# krajBB-Priezvisko_Meno.net
KiCad netlist of a schematic drawn in EAGLE
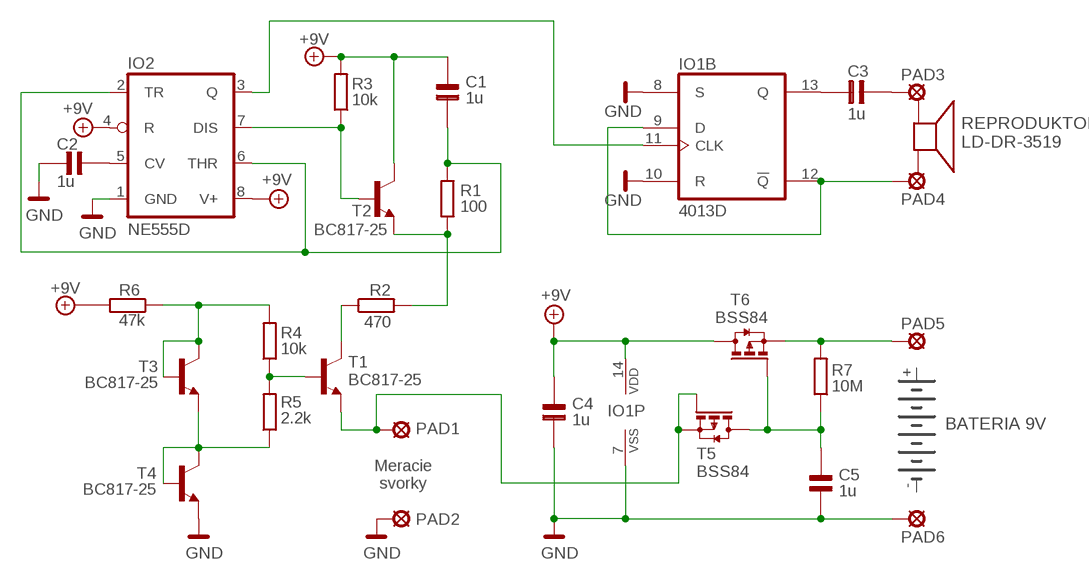
[diagram p0: schematic, sheet 1]

(export (version "E")
  (design (tool "Eeschema 10.0.6"))
  (components
    (comp (ref "C1")
      (value "1u")
      (footprint "eagle-import:1206")
      (libsource (lib "eagle-import") (part "C1206TOP"))
    )
    (comp (ref "C2")
      (value "1u")
      (footprint "eagle-import:1206")
      (libsource (lib "eagle-import") (part "C1206TOP"))
    )
    (comp (ref "C3")
      (value "1u")
      (footprint "eagle-import:1206")
      (libsource (lib "eagle-import") (part "C1206TOP"))
    )
    (comp (ref "C4")
      (value "1u")
      (footprint "eagle-import:1206")
      (libsource (lib "eagle-import") (part "C1206TOP"))
    )
    (comp (ref "C5")
      (value "1u")
      (footprint "eagle-import:1206")
      (libsource (lib "eagle-import") (part "C1206TOP"))
    )
    (comp (ref "IO1")
      (value "4013D")
      (footprint "eagle-import:SO14")
      (libsource (lib "eagle-import") (part "4013D"))
    )
    (comp (ref "IO2")
      (value "NE555D")
      (footprint "eagle-import:SO08")
      (libsource (lib "eagle-import") (part "555DNE"))
    )
    (comp (ref "PAD1")
      (value "SMD3X3")
      (footprint "eagle-import:SMD3X3")
      (libsource (lib "eagle-import") (part "SMD3X3"))
    )
    (comp (ref "PAD2")
      (value "SMD3X3")
      (footprint "eagle-import:SMD3X3")
      (libsource (lib "eagle-import") (part "SMD3X3"))
    )
    (comp (ref "PAD3")
      (value "SMD3X3")
      (footprint "eagle-import:SMD3X3")
      (libsource (lib "eagle-import") (part "SMD3X3"))
    )
    (comp (ref "PAD4")
      (value "SMD3X3")
      (footprint "eagle-import:SMD3X3")
      (libsource (lib "eagle-import") (part "SMD3X3"))
    )
    (comp (ref "PAD5")
      (value "SMD3X3")
      (footprint "eagle-import:SMD3X3")
      (libsource (lib "eagle-import") (part "SMD3X3"))
    )
    (comp (ref "PAD6")
      (value "SMD3X3")
      (footprint "eagle-import:SMD3X3")
      (libsource (lib "eagle-import") (part "SMD3X3"))
    )
    (comp (ref "R1")
      (value "100")
      (footprint "eagle-import:1206")
      (libsource (lib "eagle-import") (part "R1206TOP"))
    )
    (comp (ref "R2")
      (value "470")
      (footprint "eagle-import:1206")
      (libsource (lib "eagle-import") (part "R1206TOP"))
    )
    (comp (ref "R3")
      (value "10k")
      (footprint "eagle-import:1206")
      (libsource (lib "eagle-import") (part "R1206TOP"))
    )
    (comp (ref "R4")
      (value "10k")
      (footprint "eagle-import:1206")
      (libsource (lib "eagle-import") (part "R1206TOP"))
    )
    (comp (ref "R5")
      (value "2.2k")
      (footprint "eagle-import:1206")
      (libsource (lib "eagle-import") (part "R1206TOP"))
    )
    (comp (ref "R6")
      (value "47k")
      (footprint "eagle-import:1206")
      (libsource (lib "eagle-import") (part "R1206TOP"))
    )
    (comp (ref "R7")
      (value "10M")
      (footprint "eagle-import:1206")
      (libsource (lib "eagle-import") (part "R1206TOP"))
    )
    (comp (ref "REPRODUKTOR")
      (value "LD-DR-3519")
      (footprint "eagle-import:LD-DR-3519")
      (libsource (lib "eagle-import") (part "LD-DR-3519"))
    )
    (comp (ref "T1")
      (value "BC817-25")
      (footprint "eagle-import:SOT23-BEC")
      (libsource (lib "eagle-import") (part "BC817SMD-25"))
    )
    (comp (ref "T2")
      (value "BC817-25")
      (footprint "eagle-import:SOT23-BEC")
      (libsource (lib "eagle-import") (part "BC817SMD-25"))
    )
    (comp (ref "T3")
      (value "BC817-25")
      (footprint "eagle-import:SOT23-BEC")
      (libsource (lib "eagle-import") (part "BC817SMD-25"))
    )
    (comp (ref "T4")
      (value "BC817-25")
      (footprint "eagle-import:SOT23-BEC")
      (libsource (lib "eagle-import") (part "BC817SMD-25"))
    )
    (comp (ref "T5")
      (value "BSS84")
      (footprint "eagle-import:SOT23")
      (libsource (lib "eagle-import") (part "BSS84"))
    )
    (comp (ref "T6")
      (value "BSS84")
      (footprint "eagle-import:SOT23")
      (libsource (lib "eagle-import") (part "BSS84"))
    )
    (comp (ref "U$1")
      (value "9VBATTERY")
      (footprint "eagle-import:9VBATTERY")
      (libsource (lib "eagle-import") (part "9VBATTERY"))
    )
  )
  (nets
    (net (code "1") (name "+9V") (class "Default")
      (node (ref "C1") (pin "2") (pinfunction "2_2") (pintype "passive"))
      (node (ref "C4") (pin "2") (pinfunction "2_2") (pintype "passive"))
      (node (ref "IO1") (pin "14") (pinfunction "VDD_14") (pintype "power_in"))
      (node (ref "IO2") (pin "4") (pinfunction "R_4") (pintype "input"))
      (node (ref "IO2") (pin "8") (pinfunction "V+_8") (pintype "power_in"))
      (node (ref "R3") (pin "2") (pinfunction "2_2") (pintype "passive"))
      (node (ref "R6") (pin "2") (pinfunction "2_2") (pintype "passive"))
      (node (ref "T2") (pin "C") (pinfunction "C_C") (pintype "passive"))
      (node (ref "T6") (pin "3") (pinfunction "D_3") (pintype "passive"))
    )
    (net (code "2") (name "GND") (class "Default")
      (node (ref "C2") (pin "1") (pinfunction "1_1") (pintype "passive"))
      (node (ref "C4") (pin "1") (pinfunction "1_1") (pintype "passive"))
      (node (ref "C5") (pin "1") (pinfunction "1_1") (pintype "passive"))
      (node (ref "IO1") (pin "10") (pinfunction "R_10") (pintype "input"))
      (node (ref "IO1") (pin "7") (pinfunction "VSS_7") (pintype "power_in"))
      (node (ref "IO1") (pin "8") (pinfunction "S_8") (pintype "input"))
      (node (ref "IO2") (pin "1") (pinfunction "GND_1") (pintype "power_in"))
      (node (ref "PAD2") (pin "P$1") (pinfunction "MP_P$1") (pintype "passive"))
      (node (ref "PAD6") (pin "P$1") (pinfunction "MP_P$1") (pintype "passive"))
      (node (ref "T4") (pin "E") (pinfunction "E_E") (pintype "passive"))
    )
    (net (code "3") (name "Net-(IO1B-CLK)") (class "Default")
      (node (ref "IO1") (pin "11") (pinfunction "CLK_11") (pintype "input"))
      (node (ref "IO2") (pin "3") (pinfunction "Q_3") (pintype "output"))
    )
    (net (code "4") (name "Net-(IO1B-D)") (class "Default")
      (node (ref "IO1") (pin "12") (pinfunction "~{Q}_12") (pintype "output"))
      (node (ref "IO1") (pin "9") (pinfunction "D_9") (pintype "input"))
      (node (ref "PAD4") (pin "P$1") (pinfunction "MP_P$1") (pintype "passive"))
    )
    (net (code "5") (name "Net-(IO1B-Q)") (class "Default")
      (node (ref "C3") (pin "1") (pinfunction "1_1") (pintype "passive"))
      (node (ref "IO1") (pin "13") (pinfunction "Q_13") (pintype "output"))
    )
    (net (code "6") (name "Net-(IO2-CV)") (class "Default")
      (node (ref "C2") (pin "2") (pinfunction "2_2") (pintype "passive"))
      (node (ref "IO2") (pin "5") (pinfunction "CV_5") (pintype "input"))
    )
    (net (code "7") (name "Net-(IO2-DIS)") (class "Default")
      (node (ref "IO2") (pin "7") (pinfunction "DIS_7") (pintype "input"))
      (node (ref "R3") (pin "1") (pinfunction "1_1") (pintype "passive"))
      (node (ref "T2") (pin "B") (pinfunction "B_B") (pintype "passive"))
    )
    (net (code "8") (name "Net-(IO2-THR)") (class "Default")
      (node (ref "C1") (pin "1") (pinfunction "1_1") (pintype "passive"))
      (node (ref "IO2") (pin "2") (pinfunction "TR_2") (pintype "input"))
      (node (ref "IO2") (pin "6") (pinfunction "THR_6") (pintype "input"))
      (node (ref "R1") (pin "2") (pinfunction "2_2") (pintype "passive"))
    )
    (net (code "9") (name "Net-(PAD1-MP)") (class "Default")
      (node (ref "PAD1") (pin "P$1") (pinfunction "MP_P$1") (pintype "passive"))
      (node (ref "T1") (pin "E") (pinfunction "E_E") (pintype "passive"))
      (node (ref "T5") (pin "1") (pinfunction "G_1") (pintype "passive"))
      (node (ref "T5") (pin "2") (pinfunction "S_2") (pintype "passive"))
    )
    (net (code "10") (name "Net-(PAD3-MP)") (class "Default")
      (node (ref "C3") (pin "2") (pinfunction "2_2") (pintype "passive"))
      (node (ref "PAD3") (pin "P$1") (pinfunction "MP_P$1") (pintype "passive"))
    )
    (net (code "11") (name "Net-(PAD5-MP)") (class "Default")
      (node (ref "PAD5") (pin "P$1") (pinfunction "MP_P$1") (pintype "passive"))
      (node (ref "R7") (pin "2") (pinfunction "2_2") (pintype "passive"))
      (node (ref "T6") (pin "2") (pinfunction "S_2") (pintype "passive"))
    )
    (net (code "12") (name "Net-(R1-Pad1)") (class "Default")
      (node (ref "R1") (pin "1") (pinfunction "1_1") (pintype "passive"))
      (node (ref "R2") (pin "2") (pinfunction "2_2") (pintype "passive"))
      (node (ref "T2") (pin "E") (pinfunction "E_E") (pintype "passive"))
    )
    (net (code "13") (name "Net-(R2-Pad1)") (class "Default")
      (node (ref "R2") (pin "1") (pinfunction "1_1") (pintype "passive"))
      (node (ref "T1") (pin "C") (pinfunction "C_C") (pintype "passive"))
    )
    (net (code "14") (name "Net-(R4-Pad1)") (class "Default")
      (node (ref "R4") (pin "1") (pinfunction "1_1") (pintype "passive"))
      (node (ref "R5") (pin "2") (pinfunction "2_2") (pintype "passive"))
      (node (ref "T1") (pin "B") (pinfunction "B_B") (pintype "passive"))
    )
    (net (code "15") (name "Net-(R4-Pad2)") (class "Default")
      (node (ref "R4") (pin "2") (pinfunction "2_2") (pintype "passive"))
      (node (ref "R6") (pin "1") (pinfunction "1_1") (pintype "passive"))
      (node (ref "T3") (pin "B") (pinfunction "B_B") (pintype "passive"))
      (node (ref "T3") (pin "C") (pinfunction "C_C") (pintype "passive"))
    )
    (net (code "16") (name "Net-(R5-Pad1)") (class "Default")
      (node (ref "R5") (pin "1") (pinfunction "1_1") (pintype "passive"))
      (node (ref "T3") (pin "E") (pinfunction "E_E") (pintype "passive"))
      (node (ref "T4") (pin "B") (pinfunction "B_B") (pintype "passive"))
      (node (ref "T4") (pin "C") (pinfunction "C_C") (pintype "passive"))
    )
    (net (code "17") (name "Net-(T5-D)") (class "Default")
      (node (ref "C5") (pin "2") (pinfunction "2_2") (pintype "passive"))
      (node (ref "R7") (pin "1") (pinfunction "1_1") (pintype "passive"))
      (node (ref "T5") (pin "3") (pinfunction "D_3") (pintype "passive"))
      (node (ref "T6") (pin "1") (pinfunction "G_1") (pintype "passive"))
    )
    (net (code "18") (name "unconnected-(REPRODUKTOR-1-PadP$1)") (class "Default")
      (node (ref "REPRODUKTOR") (pin "P$1") (pinfunction "1_P$1") (pintype "passive"))
    )
    (net (code "19") (name "unconnected-(REPRODUKTOR-2-PadP$2)") (class "Default")
      (node (ref "REPRODUKTOR") (pin "P$2") (pinfunction "2_P$2") (pintype "passive"))
    )
  )
)
